# Sheet2.net
KiCad netlist of a schematic drawn in Altium Designer
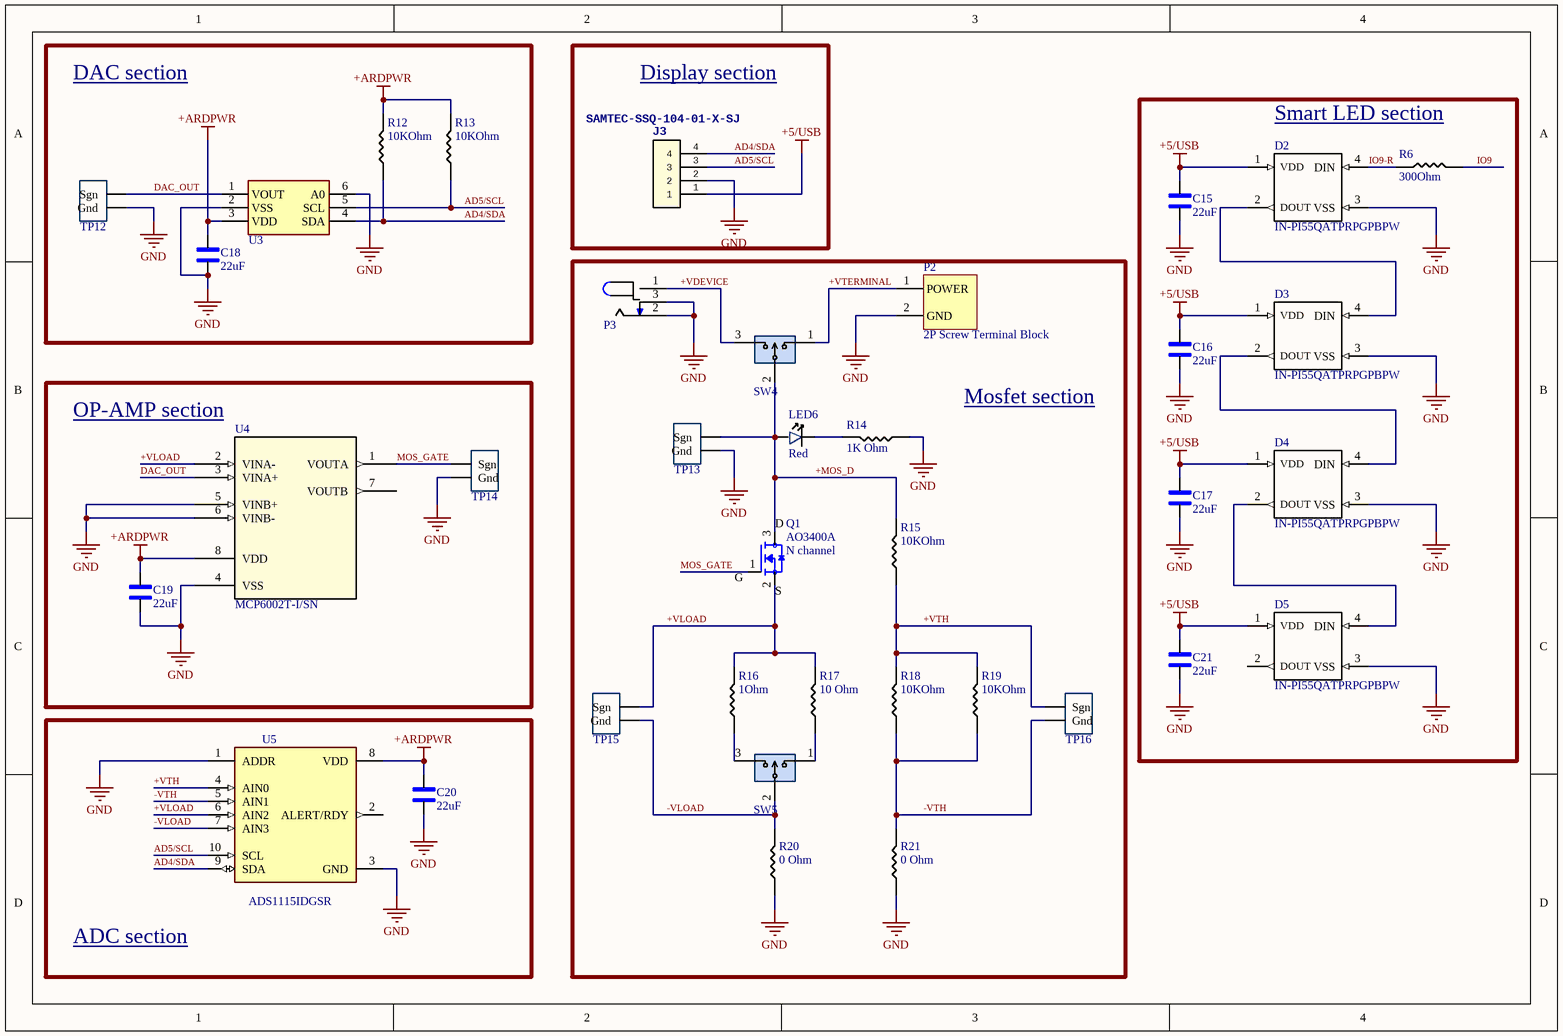
[diagram p0: Sheet2.SchDoc]

(export (version "E")
  (design (tool "Eeschema 10.0.6"))
  (components
    (comp (ref "C15")
      (value "22uF")
      (footprint "1206_Passive_Capacitor")
      (description "22uF ±10% 25V X5R 1206 Multilayer Ceramic Capacitors MLCC - SMD/SMT RoHS")
      (fields (field (name "MFR PART #") "CL31A226KAHNNNE") (field (name "LCSC PART#") "C12891"))
      (libsource (lib "ECEN5730Lib_2023_05_DS (1)") (part "C_22uF_1206"))
    )
    (comp (ref "C16")
      (value "22uF")
      (footprint "1206_Passive_Capacitor")
      (description "22uF ±10% 25V X5R 1206 Multilayer Ceramic Capacitors MLCC - SMD/SMT RoHS")
      (fields (field (name "MFR PART #") "CL31A226KAHNNNE") (field (name "LCSC PART#") "C12891"))
      (libsource (lib "ECEN5730Lib_2023_05_DS (1)") (part "C_22uF_1206"))
    )
    (comp (ref "C17")
      (value "22uF")
      (footprint "1206_Passive_Capacitor")
      (description "22uF ±10% 25V X5R 1206 Multilayer Ceramic Capacitors MLCC - SMD/SMT RoHS")
      (fields (field (name "MFR PART #") "CL31A226KAHNNNE") (field (name "LCSC PART#") "C12891"))
      (libsource (lib "ECEN5730Lib_2023_05_DS (1)") (part "C_22uF_1206"))
    )
    (comp (ref "C18")
      (value "22uF")
      (footprint "1206_Passive_Capacitor")
      (description "22uF ±10% 25V X5R 1206 Multilayer Ceramic Capacitors MLCC - SMD/SMT RoHS")
      (fields (field (name "MFR PART #") "CL31A226KAHNNNE") (field (name "LCSC PART#") "C12891"))
      (libsource (lib "ECEN5730Lib_2023_05_DS (1)") (part "C_22uF_1206"))
    )
    (comp (ref "C19")
      (value "22uF")
      (footprint "1206_Passive_Capacitor")
      (description "22uF ±10% 25V X5R 1206 Multilayer Ceramic Capacitors MLCC - SMD/SMT RoHS")
      (fields (field (name "MFR PART #") "CL31A226KAHNNNE") (field (name "LCSC PART#") "C12891"))
      (libsource (lib "ECEN5730Lib_2023_05_DS (1)") (part "C_22uF_1206"))
    )
    (comp (ref "C20")
      (value "22uF")
      (footprint "1206_Passive_Capacitor")
      (description "22uF ±10% 25V X5R 1206 Multilayer Ceramic Capacitors MLCC - SMD/SMT RoHS")
      (fields (field (name "MFR PART #") "CL31A226KAHNNNE") (field (name "LCSC PART#") "C12891"))
      (libsource (lib "ECEN5730Lib_2023_05_DS (1)") (part "C_22uF_1206"))
    )
    (comp (ref "C21")
      (value "22uF")
      (footprint "1206_Passive_Capacitor")
      (description "22uF ±10% 25V X5R 1206 Multilayer Ceramic Capacitors MLCC - SMD/SMT RoHS")
      (fields (field (name "MFR PART #") "CL31A226KAHNNNE") (field (name "LCSC PART#") "C12891"))
      (libsource (lib "ECEN5730Lib_2023_05_DS (1)") (part "C_22uF_1206"))
    )
    (comp (ref "D2")
      (value "IN-PI55QATPRPGPBPW")
      (footprint "SERIAL_LED - duplicate")
      (fields
        (field (name "LCSC PART#") "C2843785")
        (field (name "MFR PART #") "XL-5050RGBC-WS2812B")
        (field (name "MANUFACTURER") "XINGLIGHT")
      )
      (libsource (lib "ECEN5730Lib_2023_05_DS (1)") (part "LED_Smart"))
    )
    (comp (ref "D3")
      (value "IN-PI55QATPRPGPBPW")
      (footprint "SERIAL_LED - duplicate")
      (fields
        (field (name "LCSC PART#") "C2843785")
        (field (name "MFR PART #") "XL-5050RGBC-WS2812B")
        (field (name "MANUFACTURER") "XINGLIGHT")
      )
      (libsource (lib "ECEN5730Lib_2023_05_DS (1)") (part "LED_Smart"))
    )
    (comp (ref "D4")
      (value "IN-PI55QATPRPGPBPW")
      (footprint "SERIAL_LED - duplicate")
      (fields
        (field (name "LCSC PART#") "C2843785")
        (field (name "MFR PART #") "XL-5050RGBC-WS2812B")
        (field (name "MANUFACTURER") "XINGLIGHT")
      )
      (libsource (lib "ECEN5730Lib_2023_05_DS (1)") (part "LED_Smart"))
    )
    (comp (ref "D5")
      (value "IN-PI55QATPRPGPBPW")
      (footprint "SERIAL_LED - duplicate")
      (fields
        (field (name "LCSC PART#") "C2843785")
        (field (name "MFR PART #") "XL-5050RGBC-WS2812B")
        (field (name "MANUFACTURER") "XINGLIGHT")
      )
      (libsource (lib "ECEN5730Lib_2023_05_DS (1)") (part "LED_Smart"))
    )
    (comp (ref "J3")
      (value "SAMTEC-SSQ-104-01-X-SJ")
      (footprint "JF-4_SSQ-104-01-X-S")
      (fields (field (name "MFR PART #") "SSQ-104-01-X-SJ") (field (name "LCSC PART#") "C2718488"))
      (libsource (lib "ECEN5730Lib_2023_05_DS (1)") (part "JF_4_PIN_FEMALE"))
    )
    (comp (ref "LED6")
      (value "Red")
      (footprint "LED_1206")
      (description "Red 621~631nm 1206 Light Emitting Diodes (LED) RoHS")
      (fields (field (name "MFR PART #") "15-21/R6C-FQ1R1B/2T") (field (name "LCSC PART#") "C93133"))
      (libsource (lib "ECEN5730Lib_2023_05_DS (1)") (part "LED_RED_1206"))
    )
    (comp (ref "P2")
      (value "2P Screw Terminal Block")
      (footprint "P_Terminal block 3.5mm-pitch")
      (description "Green Straight pin 3.5mm  pitch; P=3.5mm  Screw terminal ROHS")
      (fields (field (name "MFR PART #") "KF350-3.5-2P") (field (name "MANUFACTURER") "Cixi Kefa Elec"))
      (libsource (lib "ECEN5730Lib_2023_05_DS (1)") (part "P_Terminal block"))
    )
    (comp (ref "P3")
      (value "Power Jack")
      (footprint "Power_Jack")
      (description "Power Barrel Connector Jack 2.10mm ID (0.083\"), 5.50mm OD (0.217\") Through Hole, Right Angle")
      (fields (field (name "MFR PART #") "PJ-102A") (field (name "LCSC PART#") "C136744"))
      (libsource (lib "ECEN5730Lib_2023_05_DS (1)") (part "P_Power Jack"))
    )
    (comp (ref "Q1")
      (value "AO3400A")
      (footprint "N-MOSFET")
      (description "MOSFET N Trench 30V 5.7A 1.5V @ 250uA 26.5 m? @ 5.7A,10V SOT-23-3L RoHS")
      (fields (field (name "LCSC PART#") "C20917") (field (name "ALTIUM_VALUE") "N channel"))
      (libsource (lib "ECEN5730Lib_2023_05_DS (1)") (part "Q_Nch_MOSFET"))
    )
    (comp (ref "R6")
      (value "300Ohm")
      (footprint "1206_Passive_Resitor")
      (description "CHIP RESISTOR - SURFACE MOUNT 300OHMS ±1% 1/4W 1206 ROHS")
      (fields (field (name "MFR PART #") "1206W4F3000T5E") (field (name "LCSC PART#") "C17887"))
      (libsource (lib "ECEN5730Lib_2023_05_DS (1)") (part "R_300Ohm_1206"))
    )
    (comp (ref "R12")
      (value "10KOhm")
      (footprint "1206_Passive_Resitor")
      (description "10 kOhms ±5% 0.25W, 1/4W Chip Resistor 1206 (3216 Metric) Automotive AEC-Q200 Thick Film")
      (fields (field (name "MFR PART #") "RMCF1206FT10K0") (field (name "LCSC PART#") "C17902"))
      (libsource (lib "ECEN5730Lib_2023_05_DS (1)") (part "R_10KOhm_1206"))
    )
    (comp (ref "R13")
      (value "10KOhm")
      (footprint "1206_Passive_Resitor")
      (description "10 kOhms ±5% 0.25W, 1/4W Chip Resistor 1206 (3216 Metric) Automotive AEC-Q200 Thick Film")
      (fields (field (name "MFR PART #") "RMCF1206FT10K0") (field (name "LCSC PART#") "C17902"))
      (libsource (lib "ECEN5730Lib_2023_05_DS (1)") (part "R_10KOhm_1206"))
    )
    (comp (ref "R14")
      (value "1K Ohm")
      (footprint "1206_Passive_Resitor")
      (description "CHIP RESISTOR - SURFACE MOUNT 1KOHMS ±1% 1/4W 1206 ROHS")
      (fields (field (name "MFR PART #") "RNCP1206FTD1K00CT") (field (name "LCSC PART#") "C4410"))
      (libsource (lib "ECEN5730Lib_2023_05_DS (1)") (part "R_1K_1206"))
    )
    (comp (ref "R15")
      (value "10KOhm")
      (footprint "1206_Passive_Resitor")
      (description "10 kOhms ±5% 0.25W, 1/4W Chip Resistor 1206 (3216 Metric) Automotive AEC-Q200 Thick Film")
      (fields (field (name "MFR PART #") "RMCF1206FT10K0") (field (name "LCSC PART#") "C17902"))
      (libsource (lib "ECEN5730Lib_2023_05_DS (1)") (part "R_10KOhm_1206"))
    )
    (comp (ref "R16")
      (value "1Ohm")
      (footprint "1206_Passive_Resitor")
      (description "1Ω ±5% 0.25W ±400ppm/℃ 1206 Chip Resistor - Surface Mount RoHS")
      (fields (field (name "LCSC PART#") "C1409") (field (name "MFR PART #") "1206W4J010JT5E"))
      (libsource (lib "ECEN5730Lib_2023_05_DS (1)") (part "R_1Ohm_1206"))
    )
    (comp (ref "R17")
      (value "10 Ohm")
      (footprint "1206_Passive_Resitor")
      (description "CHIP RESISTOR - SURFACE MOUNT 0.1OHMS ±1% 1/4W 1206 ROHS")
      (fields (field (name "MFR PART #") "1206W4F100JT5E") (field (name "LCSC PART#") "C17903"))
      (libsource (lib "ECEN5730Lib_2023_05_DS (1)") (part "R_10Ohm_1206"))
    )
    (comp (ref "R18")
      (value "10KOhm")
      (footprint "1206_Passive_Resitor")
      (description "10 kOhms ±5% 0.25W, 1/4W Chip Resistor 1206 (3216 Metric) Automotive AEC-Q200 Thick Film")
      (fields (field (name "MFR PART #") "RMCF1206FT10K0") (field (name "LCSC PART#") "C17902"))
      (libsource (lib "ECEN5730Lib_2023_05_DS (1)") (part "R_10KOhm_1206"))
    )
    (comp (ref "R19")
      (value "10KOhm")
      (footprint "1206_Passive_Resitor")
      (description "10 kOhms ±5% 0.25W, 1/4W Chip Resistor 1206 (3216 Metric) Automotive AEC-Q200 Thick Film")
      (fields (field (name "MFR PART #") "RMCF1206FT10K0") (field (name "LCSC PART#") "C17902"))
      (libsource (lib "ECEN5730Lib_2023_05_DS (1)") (part "R_10KOhm_1206"))
    )
    (comp (ref "R20")
      (value "0 Ohm")
      (footprint "1206_Passive_Resitor")
      (description "CHIP RESISTOR - SURFACE MOUNT 0OHMS ±1% 1/4W 1206 ROHS")
      (fields (field (name "MFR PART #") "1206W4F0000T5E") (field (name "LCSC PART#") "C17888"))
      (libsource (lib "ECEN5730Lib_2023_05_DS (1)") (part "R_0Ohm_1206"))
    )
    (comp (ref "R21")
      (value "0 Ohm")
      (footprint "1206_Passive_Resitor")
      (description "CHIP RESISTOR - SURFACE MOUNT 0OHMS ±1% 1/4W 1206 ROHS")
      (fields (field (name "MFR PART #") "1206W4F0000T5E") (field (name "LCSC PART#") "C17888"))
      (libsource (lib "ECEN5730Lib_2023_05_DS (1)") (part "R_0Ohm_1206"))
    )
    (comp (ref "SW4")
      (value "PREC003SAAN-RC")
      (footprint "3_PIN_100mil")
      (description "Connector Header Through Hole 3 position 0.100\" (2.54mm)")
      (fields (field (name "LCSC PART#") "C49257"))
      (libsource (lib "ECEN5730Lib_2023_05_DS (1)") (part "SW_3Pin_100mil_Switch"))
    )
    (comp (ref "SW5")
      (value "PREC003SAAN-RC")
      (footprint "3_PIN_100mil")
      (description "Connector Header Through Hole 3 position 0.100\" (2.54mm)")
      (fields (field (name "LCSC PART#") "C49257"))
      (libsource (lib "ECEN5730Lib_2023_05_DS (1)") (part "SW_3Pin_100mil_Switch"))
    )
    (comp (ref "TP12")
      (value "10x Probe TP")
      (footprint "TP10x_Probe")
      (description "Test Point 300 mil centers")
      (libsource (lib "") (part "TP_10x_Probe_1"))
    )
    (comp (ref "TP13")
      (value "10x Probe TP")
      (footprint "TP10x_Probe")
      (description "Test Point 300 mil centers")
      (libsource (lib "") (part "TP_10x_Probe_1"))
    )
    (comp (ref "TP14")
      (value "10x Probe TP")
      (footprint "TP10x_Probe")
      (description "Test Point 300 mil centers")
      (libsource (lib "ECEN5730Lib_2023_05_DS (1)") (part "TP_10x_Probe"))
    )
    (comp (ref "TP15")
      (value "10x Probe TP")
      (footprint "TP10x_Probe")
      (description "Test Point 300 mil centers")
      (libsource (lib "") (part "TP_10x_Probe_1"))
    )
    (comp (ref "TP16")
      (value "10x Probe TP")
      (footprint "TP10x_Probe")
      (description "Test Point 300 mil centers")
      (libsource (lib "ECEN5730Lib_2023_05_DS (1)") (part "TP_10x_Probe"))
    )
    (comp (ref "U3")
      (value "DAC IC")
      (footprint "MCP4725")
      (description "IC DAC 12BIT V-OUT SOT23-6")
      (fields (field (name "LCSC PART#") "C144198") (field (name "MFR PART #") "MCP4725A0T-E/CH"))
      (libsource (lib "ECEN5730Lib_2023_05_DS (1)") (part "U_MCP4725A0T-E/CH"))
    )
    (comp (ref "U4")
      (value "MCP6002T-I/SN")
      (footprint "SOIC127P600X175-8N")
      (description "0.6 V/us 2 1MHz 1.8V ~ 6V 100μA General Purpose SOIC-8_150mil  Operational Amplifier ROHS")
      (fields (field (name "MFR") "Microchip") (field (name "LCSC PART#") "C7377"))
      (libsource (lib "ECEN5730Lib_2023_05_DS (1)") (part "U_MCP6002T-I/SN"))
    )
    (comp (ref "U5")
      (value "ADS1115IDGSR")
      (footprint "ADC_ADS1115IDGSR")
      (description "16-Bit ADC with Integrated MUX, PGA, Comparator, Oscillator, and Reference 10-VSSOP -40 to 125")
      (fields (field (name "LCSC PART#") "C37593"))
      (libsource (lib "ECEN5730Lib_2023_05_DS (1)") (part "U_ADC_ADS1115IDGSR"))
    )
  )
  (nets
    (net (code "1") (name "+5{slash}USB") (class "Default")
      (node (ref "C15") (pin "2") (pinfunction "2_2") (pintype "passive"))
      (node (ref "C16") (pin "2") (pinfunction "2_2") (pintype "passive"))
      (node (ref "C17") (pin "2") (pinfunction "2_2") (pintype "passive"))
      (node (ref "C21") (pin "2") (pinfunction "2_2") (pintype "passive"))
      (node (ref "D2") (pin "1") (pinfunction "VDD_1") (pintype "input"))
      (node (ref "D3") (pin "1") (pinfunction "VDD_1") (pintype "input"))
      (node (ref "D4") (pin "1") (pinfunction "VDD_1") (pintype "input"))
      (node (ref "D5") (pin "1") (pinfunction "VDD_1") (pintype "input"))
      (node (ref "J3") (pin "1") (pinfunction "1_1") (pintype "passive"))
    )
    (net (code "2") (name "+ARDPWR") (class "Default")
      (node (ref "C18") (pin "2") (pinfunction "2_2") (pintype "passive"))
      (node (ref "C19") (pin "2") (pinfunction "2_2") (pintype "passive"))
      (node (ref "C20") (pin "2") (pinfunction "2_2") (pintype "passive"))
      (node (ref "R12") (pin "2") (pinfunction "2_2") (pintype "passive"))
      (node (ref "R13") (pin "2") (pinfunction "2_2") (pintype "passive"))
      (node (ref "U3") (pin "3") (pinfunction "VDD_3") (pintype "passive"))
      (node (ref "U4") (pin "8") (pinfunction "VDD_8") (pintype "passive"))
      (node (ref "U5") (pin "8") (pinfunction "VDD_8") (pintype "power_in"))
    )
    (net (code "3") (name "/+MOS_D") (class "Default")
      (node (ref "LED6") (pin "1") (pinfunction "1_1") (pintype "passive"))
      (node (ref "Q1") (pin "3") (pinfunction "D_3") (pintype "passive"))
      (node (ref "R15") (pin "2") (pinfunction "2_2") (pintype "passive"))
      (node (ref "SW4") (pin "2") (pinfunction "2_2") (pintype "passive"))
      (node (ref "TP13") (pin "1") (pinfunction "Sgn_1") (pintype "passive"))
    )
    (net (code "4") (name "/+VDEVICE") (class "Default")
      (node (ref "P3") (pin "1") (pinfunction "1_1") (pintype "power_in"))
      (node (ref "SW4") (pin "3") (pinfunction "3_3") (pintype "passive"))
    )
    (net (code "5") (name "/+VLOAD") (class "Default")
      (node (ref "Q1") (pin "2") (pinfunction "S_2") (pintype "passive"))
      (node (ref "R16") (pin "2") (pinfunction "2_2") (pintype "passive"))
      (node (ref "R17") (pin "2") (pinfunction "2_2") (pintype "passive"))
      (node (ref "TP15") (pin "1") (pinfunction "Sgn_1") (pintype "passive"))
      (node (ref "U4") (pin "2") (pinfunction "VINA-_2") (pintype "input"))
      (node (ref "U5") (pin "6") (pinfunction "AIN2_6") (pintype "input"))
    )
    (net (code "6") (name "/+VTERMINAL") (class "Default")
      (node (ref "P2") (pin "1") (pinfunction "POWER_1") (pintype "passive"))
      (node (ref "SW4") (pin "1") (pinfunction "1_1") (pintype "passive"))
    )
    (net (code "7") (name "/+VTH") (class "Default")
      (node (ref "R15") (pin "1") (pinfunction "1_1") (pintype "passive"))
      (node (ref "R18") (pin "2") (pinfunction "2_2") (pintype "passive"))
      (node (ref "R19") (pin "2") (pinfunction "2_2") (pintype "passive"))
      (node (ref "TP16") (pin "1") (pinfunction "Sgn_1") (pintype "passive"))
      (node (ref "U5") (pin "4") (pinfunction "AIN0_4") (pintype "input"))
    )
    (net (code "8") (name "/-VLOAD") (class "Default")
      (node (ref "R20") (pin "2") (pinfunction "2_2") (pintype "passive"))
      (node (ref "SW5") (pin "2") (pinfunction "2_2") (pintype "passive"))
      (node (ref "TP15") (pin "2") (pinfunction "Gnd_2") (pintype "passive"))
      (node (ref "U5") (pin "7") (pinfunction "AIN3_7") (pintype "input"))
    )
    (net (code "9") (name "/-VTH") (class "Default")
      (node (ref "R18") (pin "1") (pinfunction "1_1") (pintype "passive"))
      (node (ref "R19") (pin "1") (pinfunction "1_1") (pintype "passive"))
      (node (ref "R21") (pin "2") (pinfunction "2_2") (pintype "passive"))
      (node (ref "TP16") (pin "2") (pinfunction "Gnd_2") (pintype "passive"))
      (node (ref "U5") (pin "5") (pinfunction "AIN1_5") (pintype "input"))
    )
    (net (code "10") (name "/AD4{slash}SDA") (class "Default")
      (node (ref "J3") (pin "4") (pinfunction "4_4") (pintype "passive"))
      (node (ref "R12") (pin "1") (pinfunction "1_1") (pintype "passive"))
      (node (ref "U3") (pin "4") (pinfunction "SDA_4") (pintype "passive"))
      (node (ref "U5") (pin "9") (pinfunction "SDA_9") (pintype "bidirectional"))
    )
    (net (code "11") (name "/AD5{slash}SCL") (class "Default")
      (node (ref "J3") (pin "3") (pinfunction "3_3") (pintype "passive"))
      (node (ref "R13") (pin "1") (pinfunction "1_1") (pintype "passive"))
      (node (ref "U3") (pin "5") (pinfunction "SCL_5") (pintype "passive"))
      (node (ref "U5") (pin "10") (pinfunction "SCL_10") (pintype "input"))
    )
    (net (code "12") (name "/DAC_OUT") (class "Default")
      (node (ref "TP12") (pin "1") (pinfunction "Sgn_1") (pintype "passive"))
      (node (ref "U3") (pin "1") (pinfunction "VOUT_1") (pintype "passive"))
      (node (ref "U4") (pin "3") (pinfunction "VINA+_3") (pintype "input"))
    )
    (net (code "13") (name "/IO9") (class "Default")
      (node (ref "R6") (pin "2") (pinfunction "2_2") (pintype "passive"))
    )
    (net (code "14") (name "/IO9-R") (class "Default")
      (node (ref "D2") (pin "4") (pinfunction "DIN_4") (pintype "input"))
      (node (ref "R6") (pin "1") (pinfunction "1_1") (pintype "passive"))
    )
    (net (code "15") (name "/MOS_GATE") (class "Default")
      (node (ref "Q1") (pin "1") (pinfunction "G_1") (pintype "passive"))
      (node (ref "TP14") (pin "1") (pinfunction "Sgn_1") (pintype "passive"))
      (node (ref "U4") (pin "1") (pinfunction "VOUTA_1") (pintype "output"))
    )
    (net (code "16") (name "GND") (class "Default")
      (node (ref "C15") (pin "1") (pinfunction "1_1") (pintype "passive"))
      (node (ref "C16") (pin "1") (pinfunction "1_1") (pintype "passive"))
      (node (ref "C17") (pin "1") (pinfunction "1_1") (pintype "passive"))
      (node (ref "C18") (pin "1") (pinfunction "1_1") (pintype "passive"))
      (node (ref "C19") (pin "1") (pinfunction "1_1") (pintype "passive"))
      (node (ref "C20") (pin "1") (pinfunction "1_1") (pintype "passive"))
      (node (ref "C21") (pin "1") (pinfunction "1_1") (pintype "passive"))
      (node (ref "D2") (pin "3") (pinfunction "VSS_3") (pintype "input"))
      (node (ref "D3") (pin "3") (pinfunction "VSS_3") (pintype "input"))
      (node (ref "D4") (pin "3") (pinfunction "VSS_3") (pintype "input"))
      (node (ref "D5") (pin "3") (pinfunction "VSS_3") (pintype "input"))
      (node (ref "J3") (pin "2") (pinfunction "2_2") (pintype "passive"))
      (node (ref "P2") (pin "2") (pinfunction "GND_2") (pintype "passive"))
      (node (ref "P3") (pin "2") (pinfunction "2_2") (pintype "power_in"))
      (node (ref "P3") (pin "3") (pinfunction "3_3") (pintype "power_in"))
      (node (ref "R14") (pin "1") (pinfunction "1_1") (pintype "passive"))
      (node (ref "R20") (pin "1") (pinfunction "1_1") (pintype "passive"))
      (node (ref "R21") (pin "1") (pinfunction "1_1") (pintype "passive"))
      (node (ref "TP12") (pin "2") (pinfunction "Gnd_2") (pintype "passive"))
      (node (ref "TP13") (pin "2") (pinfunction "Gnd_2") (pintype "passive"))
      (node (ref "TP14") (pin "2") (pinfunction "Gnd_2") (pintype "passive"))
      (node (ref "U3") (pin "2") (pinfunction "VSS_2") (pintype "passive"))
      (node (ref "U3") (pin "6") (pinfunction "A0_6") (pintype "passive"))
      (node (ref "U4") (pin "4") (pinfunction "VSS_4") (pintype "passive"))
      (node (ref "U4") (pin "5") (pinfunction "VINB+_5") (pintype "input"))
      (node (ref "U4") (pin "6") (pinfunction "VINB-_6") (pintype "input"))
      (node (ref "U5") (pin "1") (pinfunction "ADDR_1") (pintype "passive"))
      (node (ref "U5") (pin "3") (pinfunction "GND_3") (pintype "power_in"))
    )
    (net (code "17") (name "Net-(D2-DOUT)") (class "Default")
      (node (ref "D2") (pin "2") (pinfunction "DOUT_2") (pintype "output"))
      (node (ref "D3") (pin "4") (pinfunction "DIN_4") (pintype "input"))
    )
    (net (code "18") (name "Net-(D3-DOUT)") (class "Default")
      (node (ref "D3") (pin "2") (pinfunction "DOUT_2") (pintype "output"))
      (node (ref "D4") (pin "4") (pinfunction "DIN_4") (pintype "input"))
    )
    (net (code "19") (name "Net-(D4-DOUT)") (class "Default")
      (node (ref "D4") (pin "2") (pinfunction "DOUT_2") (pintype "output"))
      (node (ref "D5") (pin "4") (pinfunction "DIN_4") (pintype "input"))
    )
    (net (code "20") (name "Net-(LED6-Pad2)") (class "Default")
      (node (ref "LED6") (pin "2") (pinfunction "2_2") (pintype "passive"))
      (node (ref "R14") (pin "2") (pinfunction "2_2") (pintype "passive"))
    )
    (net (code "21") (name "Net-(R16-Pad1)") (class "Default")
      (node (ref "R16") (pin "1") (pinfunction "1_1") (pintype "passive"))
      (node (ref "SW5") (pin "3") (pinfunction "3_3") (pintype "passive"))
    )
    (net (code "22") (name "Net-(R17-Pad1)") (class "Default")
      (node (ref "R17") (pin "1") (pinfunction "1_1") (pintype "passive"))
      (node (ref "SW5") (pin "1") (pinfunction "1_1") (pintype "passive"))
    )
    (net (code "23") (name "unconnected-(D5-DOUT-Pad2)") (class "Default")
      (node (ref "D5") (pin "2") (pinfunction "DOUT_2") (pintype "output"))
    )
    (net (code "24") (name "unconnected-(U4-VOUTB-Pad7)") (class "Default")
      (node (ref "U4") (pin "7") (pinfunction "VOUTB_7") (pintype "output"))
    )
    (net (code "25") (name "unconnected-(U5-ALERT{slash}RDY-Pad2)") (class "Default")
      (node (ref "U5") (pin "2") (pinfunction "ALERT/RDY_2") (pintype "output"))
    )
  )
)
